# PWM_Module.net
KiCad netlist of a schematic drawn in EAGLE
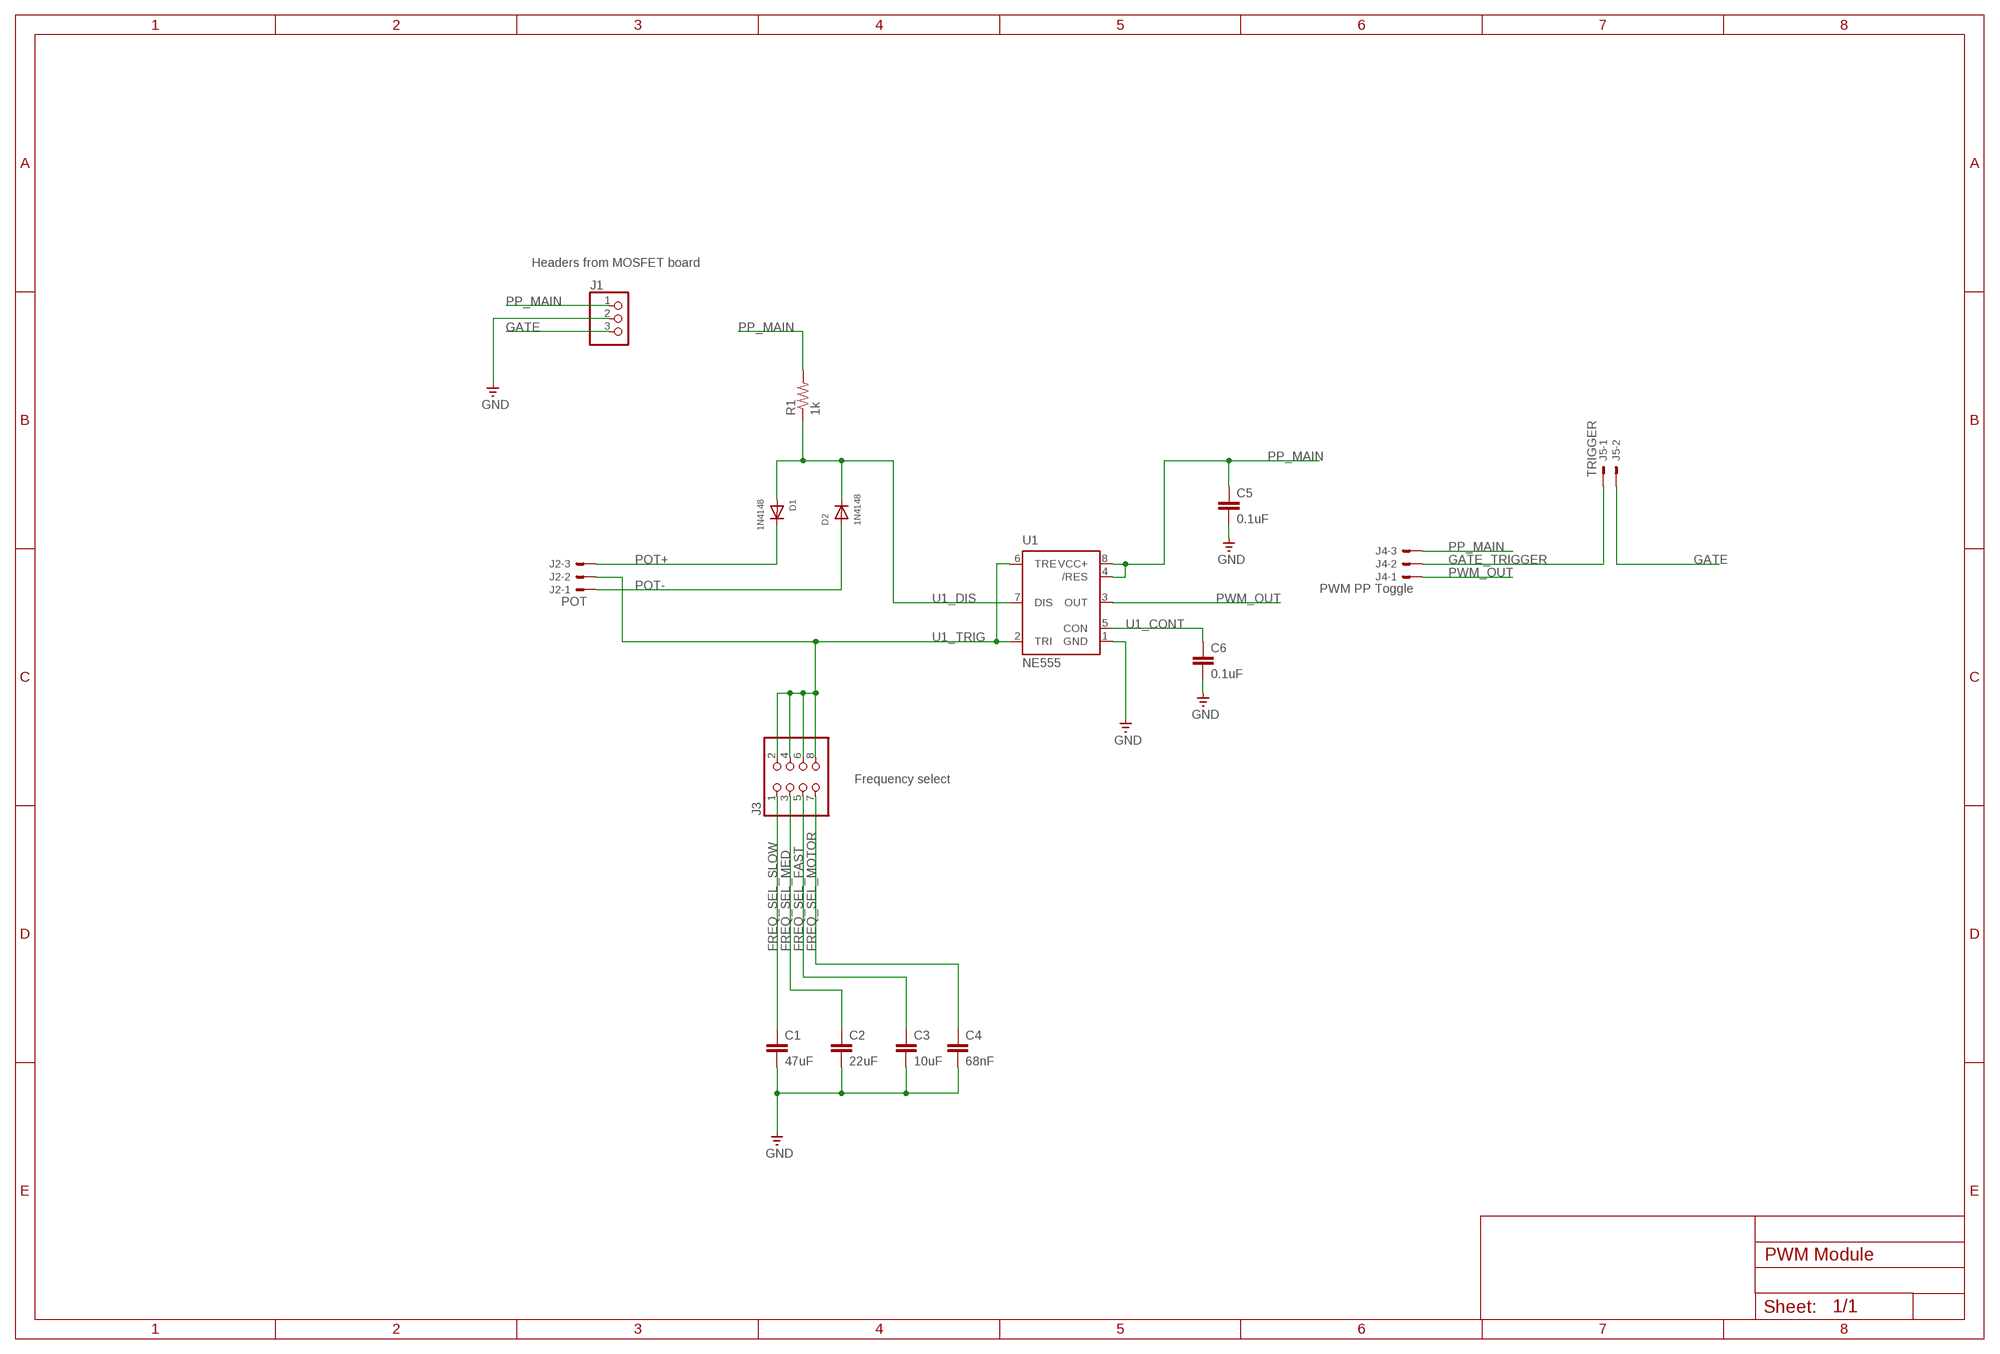
[diagram p0: schematic, sheet 1]

(export (version "E")
  (design (tool "Eeschema 10.0.6"))
  (components
    (comp (ref "C1")
      (value "47uF")
      (footprint "eagle-import:C1210")
      (libsource (lib "eagle-import") (part "CC1210"))
    )
    (comp (ref "C2")
      (value "22uF")
      (footprint "eagle-import:C1206")
      (libsource (lib "eagle-import") (part "CC1206"))
    )
    (comp (ref "C3")
      (value "10uF")
      (footprint "eagle-import:C1206")
      (libsource (lib "eagle-import") (part "CC1206"))
    )
    (comp (ref "C4")
      (value "68nF")
      (footprint "eagle-import:C0805")
      (libsource (lib "eagle-import") (part "C-EUC0805"))
    )
    (comp (ref "C5")
      (value "0.1uF")
      (footprint "eagle-import:C0805")
      (libsource (lib "eagle-import") (part "C-EUC0805"))
    )
    (comp (ref "C6")
      (value "0.1uF")
      (footprint "eagle-import:C0805")
      (libsource (lib "eagle-import") (part "C-EUC0805"))
    )
    (comp (ref "D1")
      (value "1N4148")
      (footprint "eagle-import:DO-1N4148")
      (libsource (lib "eagle-import") (part "DIODEDO-1N4148"))
    )
    (comp (ref "D2")
      (value "1N4148")
      (footprint "eagle-import:DO-1N4148")
      (libsource (lib "eagle-import") (part "DIODEDO-1N4148"))
    )
    (comp (ref "J1")
      (value "PINHD-1X3")
      (footprint "eagle-import:1X03")
      (libsource (lib "eagle-import") (part "PINHD-1X3"))
    )
    (comp (ref "J2")
      (value "POT")
      (footprint "eagle-import:JST-XH-03-PACKAGE-LONG-PAD")
      (libsource (lib "eagle-import") (part "JST-XH-03-PIN-LONG-PAD"))
    )
    (comp (ref "J3")
      (value "PINHD-2X4")
      (footprint "eagle-import:2X04")
      (libsource (lib "eagle-import") (part "PINHD-2X4"))
    )
    (comp (ref "J4")
      (value "PWM PP Toggle")
      (footprint "eagle-import:JST-XH-03-PACKAGE-LONG-PAD")
      (libsource (lib "eagle-import") (part "JST-XH-03-PIN-LONG-PAD"))
    )
    (comp (ref "J5")
      (value "TRIGGER")
      (footprint "eagle-import:JST-XH-02-PACKAGE-LONG-PAD")
      (libsource (lib "eagle-import") (part "JST-XH-02-PIN-LONG-PAD"))
    )
    (comp (ref "R1")
      (value "1k")
      (footprint "eagle-import:R0805")
      (libsource (lib "eagle-import") (part "R-US_R0805"))
    )
    (comp (ref "U1")
      (value "NE555")
      (footprint "eagle-import:DIL-08")
      (fields (field (name "MF") "Arrow Electronics") (field (name "MPN") "NE555N"))
      (libsource (lib "eagle-import") (part "NE555"))
    )
  )
  (nets
    (net (code "1") (name "/FREQ_SEL_FAST") (class "Default")
      (node (ref "C3") (pin "1") (pinfunction "1_1") (pintype "passive"))
      (node (ref "J3") (pin "5") (pinfunction "5_5") (pintype "passive"))
    )
    (net (code "2") (name "/FREQ_SEL_MED") (class "Default")
      (node (ref "C2") (pin "1") (pinfunction "1_1") (pintype "passive"))
      (node (ref "J3") (pin "3") (pinfunction "3_3") (pintype "passive"))
    )
    (net (code "3") (name "/FREQ_SEL_MOTOR") (class "Default")
      (node (ref "C4") (pin "1") (pinfunction "1_1") (pintype "passive"))
      (node (ref "J3") (pin "7") (pinfunction "7_7") (pintype "passive"))
    )
    (net (code "4") (name "/FREQ_SEL_SLOW") (class "Default")
      (node (ref "C1") (pin "1") (pinfunction "1_1") (pintype "passive"))
      (node (ref "J3") (pin "1") (pinfunction "1_1") (pintype "passive"))
    )
    (net (code "5") (name "/GATE") (class "Default")
      (node (ref "J1") (pin "3") (pinfunction "3_3") (pintype "passive"))
      (node (ref "J5") (pin "2") (pinfunction "S_2") (pintype "passive"))
    )
    (net (code "6") (name "/GATE_TRIGGER") (class "Default")
      (node (ref "J4") (pin "2") (pinfunction "S_2") (pintype "passive"))
      (node (ref "J5") (pin "1") (pinfunction "S_1") (pintype "passive"))
    )
    (net (code "7") (name "/POT+") (class "Default")
      (node (ref "D1") (pin "C") (pinfunction "C_C") (pintype "passive"))
      (node (ref "J2") (pin "3") (pinfunction "S_3") (pintype "passive"))
    )
    (net (code "8") (name "/POT-") (class "Default")
      (node (ref "D2") (pin "A") (pinfunction "A_A") (pintype "passive"))
      (node (ref "J2") (pin "1") (pinfunction "S_1") (pintype "passive"))
    )
    (net (code "9") (name "/PP_MAIN") (class "Default")
      (node (ref "C5") (pin "1") (pinfunction "1_1") (pintype "passive"))
      (node (ref "J1") (pin "1") (pinfunction "1_1") (pintype "passive"))
      (node (ref "J4") (pin "3") (pinfunction "S_3") (pintype "passive"))
      (node (ref "R1") (pin "2") (pinfunction "2_2") (pintype "passive"))
      (node (ref "U1") (pin "4") (pinfunction "/RES_4") (pintype "input"))
      (node (ref "U1") (pin "8") (pinfunction "VCC+_8") (pintype "power_in"))
    )
    (net (code "10") (name "/PWM_OUT") (class "Default")
      (node (ref "J4") (pin "1") (pinfunction "S_1") (pintype "passive"))
      (node (ref "U1") (pin "3") (pinfunction "OUT_3") (pintype "output"))
    )
    (net (code "11") (name "/U1_CONT") (class "Default")
      (node (ref "C6") (pin "1") (pinfunction "1_1") (pintype "passive"))
      (node (ref "U1") (pin "5") (pinfunction "CON_5") (pintype "input"))
    )
    (net (code "12") (name "/U1_DIS") (class "Default")
      (node (ref "D1") (pin "A") (pinfunction "A_A") (pintype "passive"))
      (node (ref "D2") (pin "C") (pinfunction "C_C") (pintype "passive"))
      (node (ref "R1") (pin "1") (pinfunction "1_1") (pintype "passive"))
      (node (ref "U1") (pin "7") (pinfunction "DIS_7") (pintype "input"))
    )
    (net (code "13") (name "/U1_TRIG") (class "Default")
      (node (ref "J2") (pin "2") (pinfunction "S_2") (pintype "passive"))
      (node (ref "J3") (pin "2") (pinfunction "2_2") (pintype "passive"))
      (node (ref "J3") (pin "4") (pinfunction "4_4") (pintype "passive"))
      (node (ref "J3") (pin "6") (pinfunction "6_6") (pintype "passive"))
      (node (ref "J3") (pin "8") (pinfunction "8_8") (pintype "passive"))
      (node (ref "U1") (pin "2") (pinfunction "TRI_2") (pintype "input"))
      (node (ref "U1") (pin "6") (pinfunction "TRE_6") (pintype "input"))
    )
    (net (code "14") (name "GND") (class "Default")
      (node (ref "C1") (pin "2") (pinfunction "2_2") (pintype "passive"))
      (node (ref "C2") (pin "2") (pinfunction "2_2") (pintype "passive"))
      (node (ref "C3") (pin "2") (pinfunction "2_2") (pintype "passive"))
      (node (ref "C4") (pin "2") (pinfunction "2_2") (pintype "passive"))
      (node (ref "C5") (pin "2") (pinfunction "2_2") (pintype "passive"))
      (node (ref "C6") (pin "2") (pinfunction "2_2") (pintype "passive"))
      (node (ref "J1") (pin "2") (pinfunction "2_2") (pintype "passive"))
      (node (ref "U1") (pin "1") (pinfunction "GND_1") (pintype "power_in"))
    )
  )
)
